# arduino_mega_2.net
KiCad netlist of a schematic drawn in EAGLE
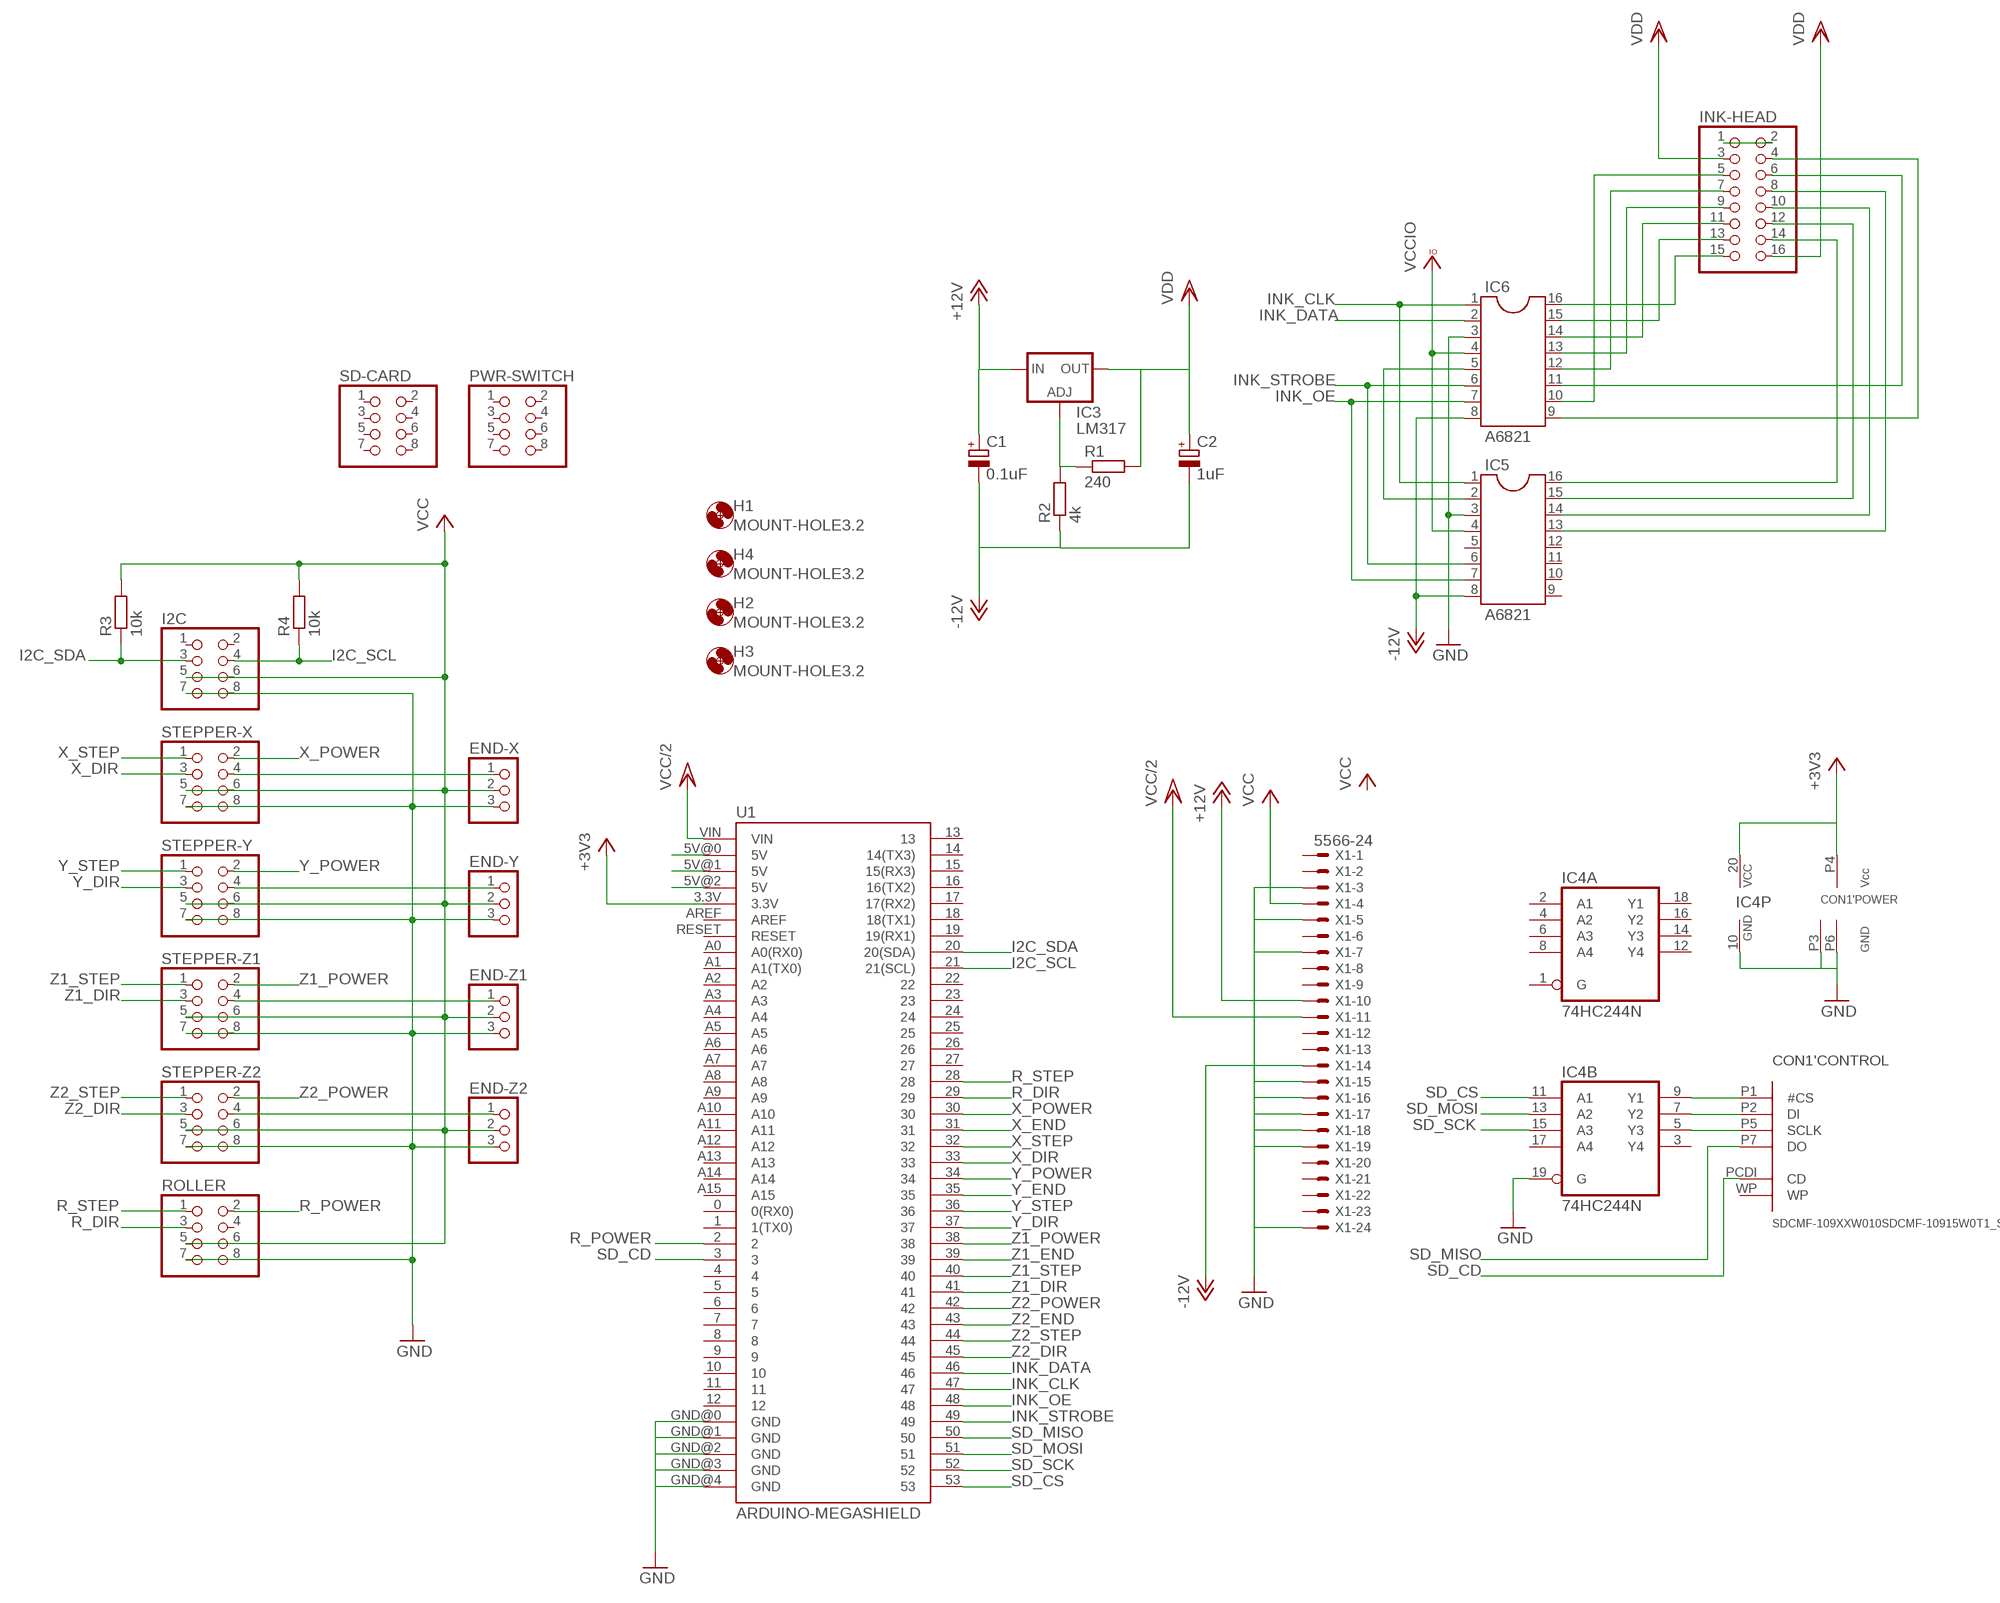
[diagram p0: schematic, sheet 1]

(export (version "E")
  (design (tool "Eeschema 10.0.6"))
  (components
    (comp (ref "C1")
      (value "0.1uF")
      (footprint "eagle-import:E2-5")
      (libsource (lib "eagle-import") (part "CPOL-EUE2-5"))
    )
    (comp (ref "C2")
      (value "1uF")
      (footprint "eagle-import:E2-5")
      (libsource (lib "eagle-import") (part "CPOL-EUE2-5"))
    )
    (comp (ref "CON1")
      (value "SDCMF-109XXW010SDCMF-10915W0T1_SO")
      (footprint "eagle-import:SDCMF-10915W0T1")
      (libsource (lib "eagle-import") (part "SDCMF-109XXW010SDCMF-10915W0T1_SO"))
    )
    (comp (ref "END-X")
      (value "PINHD-1X3")
      (footprint "eagle-import:1X03")
      (libsource (lib "eagle-import") (part "PINHD-1X3"))
    )
    (comp (ref "END-Y")
      (value "PINHD-1X3")
      (footprint "eagle-import:1X03")
      (libsource (lib "eagle-import") (part "PINHD-1X3"))
    )
    (comp (ref "END-Z1")
      (value "PINHD-1X3")
      (footprint "eagle-import:1X03")
      (libsource (lib "eagle-import") (part "PINHD-1X3"))
    )
    (comp (ref "END-Z2")
      (value "PINHD-1X3")
      (footprint "eagle-import:1X03")
      (libsource (lib "eagle-import") (part "PINHD-1X3"))
    )
    (comp (ref "H1")
      (value "MOUNT-HOLE3.2")
      (footprint "eagle-import:3,2")
      (libsource (lib "eagle-import") (part "MOUNT-HOLE3.2"))
    )
    (comp (ref "H2")
      (value "MOUNT-HOLE3.2")
      (footprint "eagle-import:3,2")
      (libsource (lib "eagle-import") (part "MOUNT-HOLE3.2"))
    )
    (comp (ref "H3")
      (value "MOUNT-HOLE3.2")
      (footprint "eagle-import:3,2")
      (libsource (lib "eagle-import") (part "MOUNT-HOLE3.2"))
    )
    (comp (ref "H4")
      (value "MOUNT-HOLE3.2")
      (footprint "eagle-import:3,2")
      (libsource (lib "eagle-import") (part "MOUNT-HOLE3.2"))
    )
    (comp (ref "I2C")
      (value "PINHD-2X4")
      (footprint "eagle-import:2X04")
      (libsource (lib "eagle-import") (part "PINHD-2X4"))
    )
    (comp (ref "IC3")
      (value "LM317")
      (footprint "eagle-import:317TL")
      (libsource (lib "eagle-import") (part "LM317TL"))
    )
    (comp (ref "IC4")
      (value "74HC244N")
      (footprint "eagle-import:DIL20")
      (libsource (lib "eagle-import") (part "74244NHC"))
    )
    (comp (ref "IC5")
      (value "A6821")
      (footprint "eagle-import:DIL16")
      (libsource (lib "eagle-import") (part "DIL16"))
    )
    (comp (ref "IC6")
      (value "A6821")
      (footprint "eagle-import:DIL16")
      (libsource (lib "eagle-import") (part "DIL16"))
    )
    (comp (ref "INK-HEAD")
      (value "PINHD-2X8")
      (footprint "eagle-import:2X08")
      (libsource (lib "eagle-import") (part "PINHD-2X8"))
    )
    (comp (ref "PWR-SWITCH")
      (value "PINHD-2X4")
      (footprint "eagle-import:2X04")
      (libsource (lib "eagle-import") (part "PINHD-2X4"))
    )
    (comp (ref "R1")
      (value "240")
      (footprint "eagle-import:0207_10")
      (libsource (lib "eagle-import") (part "R-EU_0207/10"))
    )
    (comp (ref "R2")
      (value "4k")
      (footprint "eagle-import:0207_10")
      (libsource (lib "eagle-import") (part "R-EU_0207/10"))
    )
    (comp (ref "R3")
      (value "10k")
      (footprint "eagle-import:0204_7")
      (libsource (lib "eagle-import") (part "R-EU_0204/7"))
    )
    (comp (ref "R4")
      (value "10k")
      (footprint "eagle-import:0204_7")
      (libsource (lib "eagle-import") (part "R-EU_0204/7"))
    )
    (comp (ref "ROLLER")
      (value "PINHD-2X4")
      (footprint "eagle-import:2X04")
      (libsource (lib "eagle-import") (part "PINHD-2X4"))
    )
    (comp (ref "SD-CARD")
      (value "PINHD-2X4")
      (footprint "eagle-import:2X04")
      (libsource (lib "eagle-import") (part "PINHD-2X4"))
    )
    (comp (ref "STEPPER-X")
      (value "PINHD-2X4")
      (footprint "eagle-import:2X04")
      (libsource (lib "eagle-import") (part "PINHD-2X4"))
    )
    (comp (ref "STEPPER-Y")
      (value "PINHD-2X4")
      (footprint "eagle-import:2X04")
      (libsource (lib "eagle-import") (part "PINHD-2X4"))
    )
    (comp (ref "STEPPER-Z1")
      (value "PINHD-2X4")
      (footprint "eagle-import:2X04")
      (libsource (lib "eagle-import") (part "PINHD-2X4"))
    )
    (comp (ref "STEPPER-Z2")
      (value "PINHD-2X4")
      (footprint "eagle-import:2X04")
      (libsource (lib "eagle-import") (part "PINHD-2X4"))
    )
    (comp (ref "U1")
      (value "ARDUINO-MEGASHIELD")
      (footprint "eagle-import:ARDUINO_MEGA_SHIELD")
      (libsource (lib "eagle-import") (part "ARDUINO-MEGASHIELD"))
    )
    (comp (ref "X1")
      (value "5566-24")
      (footprint "eagle-import:5566-24")
      (libsource (lib "eagle-import") (part "5566-24"))
    )
  )
  (nets
    (net (code "1") (name "+3V3") (class "Default")
      (node (ref "CON1") (pin "P4") (pinfunction "VCC_P4") (pintype "power_in"))
      (node (ref "IC4") (pin "20") (pinfunction "VCC_20") (pintype "power_in"))
      (node (ref "U1") (pin "3.3V") (pinfunction "3.3V_3.3V") (pintype "bidirectional"))
    )
    (net (code "2") (name "+12V") (class "Default")
      (node (ref "C1") (pin "+") (pinfunction "+_+") (pintype "passive"))
      (node (ref "IC3") (pin "3") (pinfunction "IN_3") (pintype "input"))
      (node (ref "X1") (pin "10") (pinfunction "S_10") (pintype "passive"))
    )
    (net (code "3") (name "-12V") (class "Default")
      (node (ref "C1") (pin "-") (pinfunction "-_-") (pintype "passive"))
      (node (ref "C2") (pin "-") (pinfunction "-_-") (pintype "passive"))
      (node (ref "IC5") (pin "8") (pinfunction "8_8") (pintype "passive"))
      (node (ref "IC6") (pin "8") (pinfunction "8_8") (pintype "passive"))
      (node (ref "R2") (pin "1") (pinfunction "1_1") (pintype "passive"))
      (node (ref "X1") (pin "14") (pinfunction "S_14") (pintype "passive"))
    )
    (net (code "4") (name "/I2C_SCL") (class "Default")
      (node (ref "I2C") (pin "4") (pinfunction "4_4") (pintype "passive"))
      (node (ref "R4") (pin "1") (pinfunction "1_1") (pintype "passive"))
      (node (ref "U1") (pin "21") (pinfunction "21(SCL)_21") (pintype "bidirectional"))
    )
    (net (code "5") (name "/I2C_SDA") (class "Default")
      (node (ref "I2C") (pin "3") (pinfunction "3_3") (pintype "passive"))
      (node (ref "R3") (pin "1") (pinfunction "1_1") (pintype "passive"))
      (node (ref "U1") (pin "20") (pinfunction "20(SDA)_20") (pintype "bidirectional"))
    )
    (net (code "6") (name "/INK_CLK") (class "Default")
      (node (ref "IC5") (pin "1") (pinfunction "1_1") (pintype "passive"))
      (node (ref "IC6") (pin "1") (pinfunction "1_1") (pintype "passive"))
      (node (ref "U1") (pin "47") (pinfunction "47_47") (pintype "bidirectional"))
    )
    (net (code "7") (name "/INK_DATA") (class "Default")
      (node (ref "IC6") (pin "2") (pinfunction "2_2") (pintype "passive"))
      (node (ref "U1") (pin "46") (pinfunction "46_46") (pintype "bidirectional"))
    )
    (net (code "8") (name "/INK_OE") (class "Default")
      (node (ref "IC5") (pin "7") (pinfunction "7_7") (pintype "passive"))
      (node (ref "IC6") (pin "7") (pinfunction "7_7") (pintype "passive"))
      (node (ref "U1") (pin "48") (pinfunction "48_48") (pintype "bidirectional"))
    )
    (net (code "9") (name "/INK_STROBE") (class "Default")
      (node (ref "IC5") (pin "6") (pinfunction "6_6") (pintype "passive"))
      (node (ref "IC6") (pin "6") (pinfunction "6_6") (pintype "passive"))
      (node (ref "U1") (pin "49") (pinfunction "49_49") (pintype "bidirectional"))
    )
    (net (code "10") (name "/R_DIR") (class "Default")
      (node (ref "ROLLER") (pin "3") (pinfunction "3_3") (pintype "passive"))
      (node (ref "U1") (pin "29") (pinfunction "29_29") (pintype "bidirectional"))
    )
    (net (code "11") (name "/R_POWER") (class "Default")
      (node (ref "ROLLER") (pin "2") (pinfunction "2_2") (pintype "passive"))
      (node (ref "U1") (pin "2") (pinfunction "2_2") (pintype "bidirectional"))
    )
    (net (code "12") (name "/R_STEP") (class "Default")
      (node (ref "ROLLER") (pin "1") (pinfunction "1_1") (pintype "passive"))
      (node (ref "U1") (pin "28") (pinfunction "28_28") (pintype "bidirectional"))
    )
    (net (code "13") (name "/SD_CD") (class "Default")
      (node (ref "CON1") (pin "PCDI") (pinfunction "CD_PCDI") (pintype "open_collector"))
      (node (ref "U1") (pin "3") (pinfunction "3_3") (pintype "bidirectional"))
    )
    (net (code "14") (name "/SD_CS") (class "Default")
      (node (ref "IC4") (pin "11") (pinfunction "A1_11") (pintype "input"))
      (node (ref "U1") (pin "53") (pinfunction "53_53") (pintype "bidirectional"))
    )
    (net (code "15") (name "/SD_MISO") (class "Default")
      (node (ref "CON1") (pin "P7") (pinfunction "DO_P7") (pintype "output"))
      (node (ref "U1") (pin "50") (pinfunction "50_50") (pintype "bidirectional"))
    )
    (net (code "16") (name "/SD_MOSI") (class "Default")
      (node (ref "IC4") (pin "13") (pinfunction "A2_13") (pintype "input"))
      (node (ref "U1") (pin "51") (pinfunction "51_51") (pintype "bidirectional"))
    )
    (net (code "17") (name "/SD_SCK") (class "Default")
      (node (ref "IC4") (pin "15") (pinfunction "A3_15") (pintype "input"))
      (node (ref "U1") (pin "52") (pinfunction "52_52") (pintype "bidirectional"))
    )
    (net (code "18") (name "/X_DIR") (class "Default")
      (node (ref "STEPPER-X") (pin "3") (pinfunction "3_3") (pintype "passive"))
      (node (ref "U1") (pin "33") (pinfunction "33_33") (pintype "bidirectional"))
    )
    (net (code "19") (name "/X_END") (class "Default")
      (node (ref "END-X") (pin "1") (pinfunction "1_1") (pintype "passive"))
      (node (ref "STEPPER-X") (pin "4") (pinfunction "4_4") (pintype "passive"))
      (node (ref "U1") (pin "31") (pinfunction "31_31") (pintype "bidirectional"))
    )
    (net (code "20") (name "/X_POWER") (class "Default")
      (node (ref "STEPPER-X") (pin "2") (pinfunction "2_2") (pintype "passive"))
      (node (ref "U1") (pin "30") (pinfunction "30_30") (pintype "bidirectional"))
    )
    (net (code "21") (name "/X_STEP") (class "Default")
      (node (ref "STEPPER-X") (pin "1") (pinfunction "1_1") (pintype "passive"))
      (node (ref "U1") (pin "32") (pinfunction "32_32") (pintype "bidirectional"))
    )
    (net (code "22") (name "/Y_DIR") (class "Default")
      (node (ref "STEPPER-Y") (pin "3") (pinfunction "3_3") (pintype "passive"))
      (node (ref "U1") (pin "37") (pinfunction "37_37") (pintype "bidirectional"))
    )
    (net (code "23") (name "/Y_END") (class "Default")
      (node (ref "END-Y") (pin "1") (pinfunction "1_1") (pintype "passive"))
      (node (ref "STEPPER-Y") (pin "4") (pinfunction "4_4") (pintype "passive"))
      (node (ref "U1") (pin "35") (pinfunction "35_35") (pintype "bidirectional"))
    )
    (net (code "24") (name "/Y_POWER") (class "Default")
      (node (ref "STEPPER-Y") (pin "2") (pinfunction "2_2") (pintype "passive"))
      (node (ref "U1") (pin "34") (pinfunction "34_34") (pintype "bidirectional"))
    )
    (net (code "25") (name "/Y_STEP") (class "Default")
      (node (ref "STEPPER-Y") (pin "1") (pinfunction "1_1") (pintype "passive"))
      (node (ref "U1") (pin "36") (pinfunction "36_36") (pintype "bidirectional"))
    )
    (net (code "26") (name "/Z1_DIR") (class "Default")
      (node (ref "STEPPER-Z1") (pin "3") (pinfunction "3_3") (pintype "passive"))
      (node (ref "U1") (pin "41") (pinfunction "41_41") (pintype "bidirectional"))
    )
    (net (code "27") (name "/Z1_END") (class "Default")
      (node (ref "END-Z1") (pin "1") (pinfunction "1_1") (pintype "passive"))
      (node (ref "STEPPER-Z1") (pin "4") (pinfunction "4_4") (pintype "passive"))
      (node (ref "U1") (pin "39") (pinfunction "39_39") (pintype "bidirectional"))
    )
    (net (code "28") (name "/Z1_POWER") (class "Default")
      (node (ref "STEPPER-Z1") (pin "2") (pinfunction "2_2") (pintype "passive"))
      (node (ref "U1") (pin "38") (pinfunction "38_38") (pintype "bidirectional"))
    )
    (net (code "29") (name "/Z1_STEP") (class "Default")
      (node (ref "STEPPER-Z1") (pin "1") (pinfunction "1_1") (pintype "passive"))
      (node (ref "U1") (pin "40") (pinfunction "40_40") (pintype "bidirectional"))
    )
    (net (code "30") (name "/Z2_DIR") (class "Default")
      (node (ref "STEPPER-Z2") (pin "3") (pinfunction "3_3") (pintype "passive"))
      (node (ref "U1") (pin "45") (pinfunction "45_45") (pintype "bidirectional"))
    )
    (net (code "31") (name "/Z2_END") (class "Default")
      (node (ref "END-Z2") (pin "1") (pinfunction "1_1") (pintype "passive"))
      (node (ref "STEPPER-Z2") (pin "4") (pinfunction "4_4") (pintype "passive"))
      (node (ref "U1") (pin "43") (pinfunction "43_43") (pintype "bidirectional"))
    )
    (net (code "32") (name "/Z2_POWER") (class "Default")
      (node (ref "STEPPER-Z2") (pin "2") (pinfunction "2_2") (pintype "passive"))
      (node (ref "U1") (pin "42") (pinfunction "42_42") (pintype "bidirectional"))
    )
    (net (code "33") (name "/Z2_STEP") (class "Default")
      (node (ref "STEPPER-Z2") (pin "1") (pinfunction "1_1") (pintype "passive"))
      (node (ref "U1") (pin "44") (pinfunction "44_44") (pintype "bidirectional"))
    )
    (net (code "34") (name "GND") (class "Default")
      (node (ref "CON1") (pin "P3") (pinfunction "GND_P3") (pintype "power_in"))
      (node (ref "CON1") (pin "P6") (pinfunction "GND_P6") (pintype "power_in"))
      (node (ref "END-X") (pin "3") (pinfunction "3_3") (pintype "passive"))
      (node (ref "END-Y") (pin "3") (pinfunction "3_3") (pintype "passive"))
      (node (ref "END-Z1") (pin "3") (pinfunction "3_3") (pintype "passive"))
      (node (ref "END-Z2") (pin "3") (pinfunction "3_3") (pintype "passive"))
      (node (ref "I2C") (pin "7") (pinfunction "7_7") (pintype "passive"))
      (node (ref "I2C") (pin "8") (pinfunction "8_8") (pintype "passive"))
      (node (ref "IC4") (pin "10") (pinfunction "GND_10") (pintype "power_in"))
      (node (ref "IC4") (pin "19") (pinfunction "G_19") (pintype "input"))
      (node (ref "IC5") (pin "3") (pinfunction "3_3") (pintype "passive"))
      (node (ref "IC6") (pin "3") (pinfunction "3_3") (pintype "passive"))
      (node (ref "ROLLER") (pin "7") (pinfunction "7_7") (pintype "passive"))
      (node (ref "ROLLER") (pin "8") (pinfunction "8_8") (pintype "passive"))
      (node (ref "STEPPER-X") (pin "7") (pinfunction "7_7") (pintype "passive"))
      (node (ref "STEPPER-X") (pin "8") (pinfunction "8_8") (pintype "passive"))
      (node (ref "STEPPER-Y") (pin "7") (pinfunction "7_7") (pintype "passive"))
      (node (ref "STEPPER-Y") (pin "8") (pinfunction "8_8") (pintype "passive"))
      (node (ref "STEPPER-Z1") (pin "7") (pinfunction "7_7") (pintype "passive"))
      (node (ref "STEPPER-Z1") (pin "8") (pinfunction "8_8") (pintype "passive"))
      (node (ref "STEPPER-Z2") (pin "7") (pinfunction "7_7") (pintype "passive"))
      (node (ref "STEPPER-Z2") (pin "8") (pinfunction "8_8") (pintype "passive"))
      (node (ref "U1") (pin "GND@0") (pinfunction "GND_GND@0") (pintype "bidirectional"))
      (node (ref "U1") (pin "GND@1") (pinfunction "GND_GND@1") (pintype "bidirectional"))
      (node (ref "U1") (pin "GND@2") (pinfunction "GND_GND@2") (pintype "bidirectional"))
      (node (ref "U1") (pin "GND@3") (pinfunction "GND_GND@3") (pintype "bidirectional"))
      (node (ref "U1") (pin "GND@4") (pinfunction "GND_GND@4") (pintype "bidirectional"))
      (node (ref "X1") (pin "15") (pinfunction "S_15") (pintype "passive"))
      (node (ref "X1") (pin "16") (pinfunction "S_16") (pintype "passive"))
      (node (ref "X1") (pin "17") (pinfunction "S_17") (pintype "passive"))
      (node (ref "X1") (pin "18") (pinfunction "S_18") (pintype "passive"))
      (node (ref "X1") (pin "19") (pinfunction "S_19") (pintype "passive"))
      (node (ref "X1") (pin "24") (pinfunction "S_24") (pintype "passive"))
      (node (ref "X1") (pin "3") (pinfunction "S_3") (pintype "passive"))
      (node (ref "X1") (pin "5") (pinfunction "S_5") (pintype "passive"))
      (node (ref "X1") (pin "7") (pinfunction "S_7") (pintype "passive"))
    )
    (net (code "35") (name "Net-(CON1A-#CS)") (class "Default")
      (node (ref "CON1") (pin "P1") (pinfunction "#CS_P1") (pintype "input"))
      (node (ref "IC4") (pin "9") (pinfunction "Y1_9") (pintype "tri_state"))
    )
    (net (code "36") (name "Net-(CON1A-DI)") (class "Default")
      (node (ref "CON1") (pin "P2") (pinfunction "DI_P2") (pintype "input"))
      (node (ref "IC4") (pin "7") (pinfunction "Y2_7") (pintype "tri_state"))
    )
    (net (code "37") (name "Net-(CON1A-SCLK)") (class "Default")
      (node (ref "CON1") (pin "P5") (pinfunction "SCLK_P5") (pintype "input"))
      (node (ref "IC4") (pin "5") (pinfunction "Y3_5") (pintype "tri_state"))
    )
    (net (code "38") (name "Net-(IC3-ADJ)") (class "Default")
      (node (ref "IC3") (pin "1") (pinfunction "ADJ_1") (pintype "input"))
      (node (ref "R1") (pin "1") (pinfunction "1_1") (pintype "passive"))
      (node (ref "R2") (pin "2") (pinfunction "2_2") (pintype "passive"))
    )
    (net (code "39") (name "Net-(IC5-Pad2)") (class "Default")
      (node (ref "IC5") (pin "2") (pinfunction "2_2") (pintype "passive"))
      (node (ref "IC6") (pin "5") (pinfunction "5_5") (pintype "passive"))
    )
    (net (code "40") (name "Net-(IC5-Pad13)") (class "Default")
      (node (ref "IC5") (pin "13") (pinfunction "13_13") (pintype "passive"))
      (node (ref "INK-HEAD") (pin "8") (pinfunction "8_8") (pintype "passive"))
    )
    (net (code "41") (name "Net-(IC5-Pad14)") (class "Default")
      (node (ref "IC5") (pin "14") (pinfunction "14_14") (pintype "passive"))
      (node (ref "INK-HEAD") (pin "10") (pinfunction "10_10") (pintype "passive"))
    )
    (net (code "42") (name "Net-(IC5-Pad15)") (class "Default")
      (node (ref "IC5") (pin "15") (pinfunction "15_15") (pintype "passive"))
      (node (ref "INK-HEAD") (pin "12") (pinfunction "12_12") (pintype "passive"))
    )
    (net (code "43") (name "Net-(IC5-Pad16)") (class "Default")
      (node (ref "IC5") (pin "16") (pinfunction "16_16") (pintype "passive"))
      (node (ref "INK-HEAD") (pin "14") (pinfunction "14_14") (pintype "passive"))
    )
    (net (code "44") (name "Net-(IC6-Pad9)") (class "Default")
      (node (ref "IC6") (pin "9") (pinfunction "9_9") (pintype "passive"))
      (node (ref "INK-HEAD") (pin "4") (pinfunction "4_4") (pintype "passive"))
    )
    (net (code "45") (name "Net-(IC6-Pad10)") (class "Default")
      (node (ref "IC6") (pin "10") (pinfunction "10_10") (pintype "passive"))
      (node (ref "INK-HEAD") (pin "5") (pinfunction "5_5") (pintype "passive"))
    )
    (net (code "46") (name "Net-(IC6-Pad11)") (class "Default")
      (node (ref "IC6") (pin "11") (pinfunction "11_11") (pintype "passive"))
      (node (ref "INK-HEAD") (pin "6") (pinfunction "6_6") (pintype "passive"))
    )
    (net (code "47") (name "Net-(IC6-Pad12)") (class "Default")
      (node (ref "IC6") (pin "12") (pinfunction "12_12") (pintype "passive"))
      (node (ref "INK-HEAD") (pin "7") (pinfunction "7_7") (pintype "passive"))
    )
    (net (code "48") (name "Net-(IC6-Pad13)") (class "Default")
      (node (ref "IC6") (pin "13") (pinfunction "13_13") (pintype "passive"))
      (node (ref "INK-HEAD") (pin "9") (pinfunction "9_9") (pintype "passive"))
    )
    (net (code "49") (name "Net-(IC6-Pad14)") (class "Default")
      (node (ref "IC6") (pin "14") (pinfunction "14_14") (pintype "passive"))
      (node (ref "INK-HEAD") (pin "11") (pinfunction "11_11") (pintype "passive"))
    )
    (net (code "50") (name "Net-(IC6-Pad15)") (class "Default")
      (node (ref "IC6") (pin "15") (pinfunction "15_15") (pintype "passive"))
      (node (ref "INK-HEAD") (pin "13") (pinfunction "13_13") (pintype "passive"))
    )
    (net (code "51") (name "Net-(IC6-Pad16)") (class "Default")
      (node (ref "IC6") (pin "16") (pinfunction "16_16") (pintype "passive"))
      (node (ref "INK-HEAD") (pin "15") (pinfunction "15_15") (pintype "passive"))
    )
    (net (code "52") (name "Net-(INK-HEAD-Pad1)") (class "Default")
      (node (ref "INK-HEAD") (pin "1") (pinfunction "1_1") (pintype "passive"))
      (node (ref "INK-HEAD") (pin "2") (pinfunction "2_2") (pintype "passive"))
    )
    (net (code "53") (name "VCC") (class "Default")
      (node (ref "END-X") (pin "2") (pinfunction "2_2") (pintype "passive"))
      (node (ref "END-Y") (pin "2") (pinfunction "2_2") (pintype "passive"))
      (node (ref "END-Z1") (pin "2") (pinfunction "2_2") (pintype "passive"))
      (node (ref "END-Z2") (pin "2") (pinfunction "2_2") (pintype "passive"))
      (node (ref "I2C") (pin "5") (pinfunction "5_5") (pintype "passive"))
      (node (ref "I2C") (pin "6") (pinfunction "6_6") (pintype "passive"))
      (node (ref "R3") (pin "2") (pinfunction "2_2") (pintype "passive"))
      (node (ref "R4") (pin "2") (pinfunction "2_2") (pintype "passive"))
      (node (ref "ROLLER") (pin "5") (pinfunction "5_5") (pintype "passive"))
      (node (ref "ROLLER") (pin "6") (pinfunction "6_6") (pintype "passive"))
      (node (ref "STEPPER-X") (pin "5") (pinfunction "5_5") (pintype "passive"))
      (node (ref "STEPPER-X") (pin "6") (pinfunction "6_6") (pintype "passive"))
      (node (ref "STEPPER-Y") (pin "5") (pinfunction "5_5") (pintype "passive"))
      (node (ref "STEPPER-Y") (pin "6") (pinfunction "6_6") (pintype "passive"))
      (node (ref "STEPPER-Z1") (pin "5") (pinfunction "5_5") (pintype "passive"))
      (node (ref "STEPPER-Z1") (pin "6") (pinfunction "6_6") (pintype "passive"))
      (node (ref "STEPPER-Z2") (pin "5") (pinfunction "5_5") (pintype "passive"))
      (node (ref "STEPPER-Z2") (pin "6") (pinfunction "6_6") (pintype "passive"))
      (node (ref "X1") (pin "4") (pinfunction "S_4") (pintype "passive"))
    )
    (net (code "54") (name "VCCIO") (class "Default")
      (node (ref "IC5") (pin "4") (pinfunction "4_4") (pintype "passive"))
      (node (ref "IC6") (pin "4") (pinfunction "4_4") (pintype "passive"))
      (node (ref "U1") (pin "5V@0") (pinfunction "5V_5V@0") (pintype "bidirectional"))
      (node (ref "U1") (pin "5V@1") (pinfunction "5V_5V@1") (pintype "bidirectional"))
      (node (ref "U1") (pin "5V@2") (pinfunction "5V_5V@2") (pintype "bidirectional"))
    )
    (net (code "55") (name "VCC{slash}2") (class "Default")
      (node (ref "U1") (pin "VIN") (pinfunction "VIN_VIN") (pintype "bidirectional"))
      (node (ref "X1") (pin "11") (pinfunction "S_11") (pintype "passive"))
    )
    (net (code "56") (name "VDD") (class "Default")
      (node (ref "C2") (pin "+") (pinfunction "+_+") (pintype "passive"))
      (node (ref "IC3") (pin "2") (pinfunction "OUT_2") (pintype "passive"))
      (node (ref "INK-HEAD") (pin "16") (pinfunction "16_16") (pintype "passive"))
      (node (ref "INK-HEAD") (pin "3") (pinfunction "3_3") (pintype "passive"))
      (node (ref "R1") (pin "2") (pinfunction "2_2") (pintype "passive"))
    )
    (net (code "57") (name "unconnected-(CON1-PadWP)") (class "Default")
      (node (ref "CON1") (pin "WP") (pinfunction "WP_WP") (pintype "open_collector"))
    )
    (net (code "58") (name "unconnected-(I2C-Pad1)") (class "Default")
      (node (ref "I2C") (pin "1") (pinfunction "1_1") (pintype "passive"))
    )
    (net (code "59") (name "unconnected-(I2C-Pad2)") (class "Default")
      (node (ref "I2C") (pin "2") (pinfunction "2_2") (pintype "passive"))
    )
    (net (code "60") (name "unconnected-(IC4A-A1-Pad2)") (class "Default")
      (node (ref "IC4") (pin "2") (pinfunction "A1_2") (pintype "input"))
    )
    (net (code "61") (name "unconnected-(IC4A-A2-Pad4)") (class "Default")
      (node (ref "IC4") (pin "4") (pinfunction "A2_4") (pintype "input"))
    )
    (net (code "62") (name "unconnected-(IC4A-A3-Pad6)") (class "Default")
      (node (ref "IC4") (pin "6") (pinfunction "A3_6") (pintype "input"))
    )
    (net (code "63") (name "unconnected-(IC4A-A4-Pad8)") (class "Default")
      (node (ref "IC4") (pin "8") (pinfunction "A4_8") (pintype "input"))
    )
    (net (code "64") (name "unconnected-(IC4A-G-Pad1)") (class "Default")
      (node (ref "IC4") (pin "1") (pinfunction "G_1") (pintype "input"))
    )
    (net (code "65") (name "unconnected-(IC4A-Y1-Pad18)") (class "Default")
      (node (ref "IC4") (pin "18") (pinfunction "Y1_18") (pintype "tri_state"))
    )
    (net (code "66") (name "unconnected-(IC4A-Y2-Pad16)") (class "Default")
      (node (ref "IC4") (pin "16") (pinfunction "Y2_16") (pintype "tri_state"))
    )
    (net (code "67") (name "unconnected-(IC4A-Y3-Pad14)") (class "Default")
      (node (ref "IC4") (pin "14") (pinfunction "Y3_14") (pintype "tri_state"))
    )
    (net (code "68") (name "unconnected-(IC4A-Y4-Pad12)") (class "Default")
      (node (ref "IC4") (pin "12") (pinfunction "Y4_12") (pintype "tri_state"))
    )
    (net (code "69") (name "unconnected-(IC4B-A4-Pad17)") (class "Default")
      (node (ref "IC4") (pin "17") (pinfunction "A4_17") (pintype "input"))
    )
    (net (code "70") (name "unconnected-(IC4B-Y4-Pad3)") (class "Default")
      (node (ref "IC4") (pin "3") (pinfunction "Y4_3") (pintype "tri_state"))
    )
    (net (code "71") (name "unconnected-(IC5-Pad5)") (class "Default")
      (node (ref "IC5") (pin "5") (pinfunction "5_5") (pintype "passive"))
    )
    (net (code "72") (name "unconnected-(IC5-Pad9)") (class "Default")
      (node (ref "IC5") (pin "9") (pinfunction "9_9") (pintype "passive"))
    )
    (net (code "73") (name "unconnected-(IC5-Pad10)") (class "Default")
      (node (ref "IC5") (pin "10") (pinfunction "10_10") (pintype "passive"))
    )
    (net (code "74") (name "unconnected-(IC5-Pad11)") (class "Default")
      (node (ref "IC5") (pin "11") (pinfunction "11_11") (pintype "passive"))
    )
    (net (code "75") (name "unconnected-(IC5-Pad12)") (class "Default")
      (node (ref "IC5") (pin "12") (pinfunction "12_12") (pintype "passive"))
    )
    (net (code "76") (name "unconnected-(PWR-SWITCH-Pad1)") (class "Default")
      (node (ref "PWR-SWITCH") (pin "1") (pinfunction "1_1") (pintype "passive"))
    )
    (net (code "77") (name "unconnected-(PWR-SWITCH-Pad2)") (class "Default")
      (node (ref "PWR-SWITCH") (pin "2") (pinfunction "2_2") (pintype "passive"))
    )
    (net (code "78") (name "unconnected-(PWR-SWITCH-Pad3)") (class "Default")
      (node (ref "PWR-SWITCH") (pin "3") (pinfunction "3_3") (pintype "passive"))
    )
    (net (code "79") (name "unconnected-(PWR-SWITCH-Pad4)") (class "Default")
      (node (ref "PWR-SWITCH") (pin "4") (pinfunction "4_4") (pintype "passive"))
    )
    (net (code "80") (name "unconnected-(PWR-SWITCH-Pad5)") (class "Default")
      (node (ref "PWR-SWITCH") (pin "5") (pinfunction "5_5") (pintype "passive"))
    )
    (net (code "81") (name "unconnected-(PWR-SWITCH-Pad6)") (class "Default")
      (node (ref "PWR-SWITCH") (pin "6") (pinfunction "6_6") (pintype "passive"))
    )
    (net (code "82") (name "unconnected-(PWR-SWITCH-Pad7)") (class "Default")
      (node (ref "PWR-SWITCH") (pin "7") (pinfunction "7_7") (pintype "passive"))
    )
    (net (code "83") (name "unconnected-(PWR-SWITCH-Pad8)") (class "Default")
      (node (ref "PWR-SWITCH") (pin "8") (pinfunction "8_8") (pintype "passive"))
    )
    (net (code "84") (name "unconnected-(ROLLER-Pad4)") (class "Default")
      (node (ref "ROLLER") (pin "4") (pinfunction "4_4") (pintype "passive"))
    )
    (net (code "85") (name "unconnected-(SD-CARD-Pad1)") (class "Default")
      (node (ref "SD-CARD") (pin "1") (pinfunction "1_1") (pintype "passive"))
    )
    (net (code "86") (name "unconnected-(SD-CARD-Pad2)") (class "Default")
      (node (ref "SD-CARD") (pin "2") (pinfunction "2_2") (pintype "passive"))
    )
    (net (code "87") (name "unconnected-(SD-CARD-Pad3)") (class "Default")
      (node (ref "SD-CARD") (pin "3") (pinfunction "3_3") (pintype "passive"))
    )
    (net (code "88") (name "unconnected-(SD-CARD-Pad4)") (class "Default")
      (node (ref "SD-CARD") (pin "4") (pinfunction "4_4") (pintype "passive"))
    )
    (net (code "89") (name "unconnected-(SD-CARD-Pad5)") (class "Default")
      (node (ref "SD-CARD") (pin "5") (pinfunction "5_5") (pintype "passive"))
    )
    (net (code "90") (name "unconnected-(SD-CARD-Pad6)") (class "Default")
      (node (ref "SD-CARD") (pin "6") (pinfunction "6_6") (pintype "passive"))
    )
    (net (code "91") (name "unconnected-(SD-CARD-Pad7)") (class "Default")
      (node (ref "SD-CARD") (pin "7") (pinfunction "7_7") (pintype "passive"))
    )
    (net (code "92") (name "unconnected-(SD-CARD-Pad8)") (class "Default")
      (node (ref "SD-CARD") (pin "8") (pinfunction "8_8") (pintype "passive"))
    )
    (net (code "93") (name "unconnected-(U1-0(RX0)-Pad0)") (class "Default")
      (node (ref "U1") (pin "0") (pinfunction "0(RX0)_0") (pintype "bidirectional"))
    )
    (net (code "94") (name "unconnected-(U1-1(TX0)-Pad1)") (class "Default")
      (node (ref "U1") (pin "1") (pinfunction "1(TX0)_1") (pintype "bidirectional"))
    )
    (net (code "95") (name "unconnected-(U1-14(TX3)-Pad14)") (class "Default")
      (node (ref "U1") (pin "14") (pinfunction "14(TX3)_14") (pintype "bidirectional"))
    )
    (net (code "96") (name "unconnected-(U1-15(RX3)-Pad15)") (class "Default")
      (node (ref "U1") (pin "15") (pinfunction "15(RX3)_15") (pintype "bidirectional"))
    )
    (net (code "97") (name "unconnected-(U1-16(TX2)-Pad16)") (class "Default")
      (node (ref "U1") (pin "16") (pinfunction "16(TX2)_16") (pintype "bidirectional"))
    )
    (net (code "98") (name "unconnected-(U1-17(RX2)-Pad17)") (class "Default")
      (node (ref "U1") (pin "17") (pinfunction "17(RX2)_17") (pintype "bidirectional"))
    )
    (net (code "99") (name "unconnected-(U1-18(TX1)-Pad18)") (class "Default")
      (node (ref "U1") (pin "18") (pinfunction "18(TX1)_18") (pintype "bidirectional"))
    )
    (net (code "100") (name "unconnected-(U1-19(RX1)-Pad19)") (class "Default")
      (node (ref "U1") (pin "19") (pinfunction "19(RX1)_19") (pintype "bidirectional"))
    )
    (net (code "101") (name "unconnected-(U1-A0(RX0)-PadA0)") (class "Default")
      (node (ref "U1") (pin "A0") (pinfunction "A0(RX0)_A0") (pintype "bidirectional"))
    )
    (net (code "102") (name "unconnected-(U1-A1(TX0)-PadA1)") (class "Default")
      (node (ref "U1") (pin "A1") (pinfunction "A1(TX0)_A1") (pintype "bidirectional"))
    )
    (net (code "103") (name "unconnected-(U1-Pad4)") (class "Default")
      (node (ref "U1") (pin "4") (pinfunction "4_4") (pintype "bidirectional"))
    )
    (net (code "104") (name "unconnected-(U1-Pad5)") (class "Default")
      (node (ref "U1") (pin "5") (pinfunction "5_5") (pintype "bidirectional"))
    )
    (net (code "105") (name "unconnected-(U1-Pad6)") (class "Default")
      (node (ref "U1") (pin "6") (pinfunction "6_6") (pintype "bidirectional"))
    )
    (net (code "106") (name "unconnected-(U1-Pad7)") (class "Default")
      (node (ref "U1") (pin "7") (pinfunction "7_7") (pintype "bidirectional"))
    )
    (net (code "107") (name "unconnected-(U1-Pad8)") (class "Default")
      (node (ref "U1") (pin "8") (pinfunction "8_8") (pintype "bidirectional"))
    )
    (net (code "108") (name "unconnected-(U1-Pad9)") (class "Default")
      (node (ref "U1") (pin "9") (pinfunction "9_9") (pintype "bidirectional"))
    )
    (net (code "109") (name "unconnected-(U1-Pad10)") (class "Default")
      (node (ref "U1") (pin "10") (pinfunction "10_10") (pintype "bidirectional"))
    )
    (net (code "110") (name "unconnected-(U1-Pad11)") (class "Default")
      (node (ref "U1") (pin "11") (pinfunction "11_11") (pintype "bidirectional"))
    )
    (net (code "111") (name "unconnected-(U1-Pad12)") (class "Default")
      (node (ref "U1") (pin "12") (pinfunction "12_12") (pintype "bidirectional"))
    )
    (net (code "112") (name "unconnected-(U1-Pad13)") (class "Default")
      (node (ref "U1") (pin "13") (pinfunction "13_13") (pintype "bidirectional"))
    )
    (net (code "113") (name "unconnected-(U1-Pad22)") (class "Default")
      (node (ref "U1") (pin "22") (pinfunction "22_22") (pintype "bidirectional"))
    )
    (net (code "114") (name "unconnected-(U1-Pad23)") (class "Default")
      (node (ref "U1") (pin "23") (pinfunction "23_23") (pintype "bidirectional"))
    )
    (net (code "115") (name "unconnected-(U1-Pad24)") (class "Default")
      (node (ref "U1") (pin "24") (pinfunction "24_24") (pintype "bidirectional"))
    )
    (net (code "116") (name "unconnected-(U1-Pad25)") (class "Default")
      (node (ref "U1") (pin "25") (pinfunction "25_25") (pintype "bidirectional"))
    )
    (net (code "117") (name "unconnected-(U1-Pad26)") (class "Default")
      (node (ref "U1") (pin "26") (pinfunction "26_26") (pintype "bidirectional"))
    )
    (net (code "118") (name "unconnected-(U1-Pad27)") (class "Default")
      (node (ref "U1") (pin "27") (pinfunction "27_27") (pintype "bidirectional"))
    )
    (net (code "119") (name "unconnected-(U1-PadA2)") (class "Default")
      (node (ref "U1") (pin "A2") (pinfunction "A2_A2") (pintype "bidirectional"))
    )
    (net (code "120") (name "unconnected-(U1-PadA3)") (class "Default")
      (node (ref "U1") (pin "A3") (pinfunction "A3_A3") (pintype "bidirectional"))
    )
    (net (code "121") (name "unconnected-(U1-PadA4)") (class "Default")
      (node (ref "U1") (pin "A4") (pinfunction "A4_A4") (pintype "bidirectional"))
    )
    (net (code "122") (name "unconnected-(U1-PadA5)") (class "Default")
      (node (ref "U1") (pin "A5") (pinfunction "A5_A5") (pintype "bidirectional"))
    )
    (net (code "123") (name "unconnected-(U1-PadA6)") (class "Default")
      (node (ref "U1") (pin "A6") (pinfunction "A6_A6") (pintype "bidirectional"))
    )
    (net (code "124") (name "unconnected-(U1-PadA7)") (class "Default")
      (node (ref "U1") (pin "A7") (pinfunction "A7_A7") (pintype "bidirectional"))
    )
    (net (code "125") (name "unconnected-(U1-PadA8)") (class "Default")
      (node (ref "U1") (pin "A8") (pinfunction "A8_A8") (pintype "bidirectional"))
    )
    (net (code "126") (name "unconnected-(U1-PadA9)") (class "Default")
      (node (ref "U1") (pin "A9") (pinfunction "A9_A9") (pintype "bidirectional"))
    )
    (net (code "127") (name "unconnected-(U1-PadA10)") (class "Default")
      (node (ref "U1") (pin "A10") (pinfunction "A10_A10") (pintype "bidirectional"))
    )
    (net (code "128") (name "unconnected-(U1-PadA11)") (class "Default")
      (node (ref "U1") (pin "A11") (pinfunction "A11_A11") (pintype "bidirectional"))
    )
    (net (code "129") (name "unconnected-(U1-PadA12)") (class "Default")
      (node (ref "U1") (pin "A12") (pinfunction "A12_A12") (pintype "bidirectional"))
    )
    (net (code "130") (name "unconnected-(U1-PadA13)") (class "Default")
      (node (ref "U1") (pin "A13") (pinfunction "A13_A13") (pintype "bidirectional"))
    )
    (net (code "131") (name "unconnected-(U1-PadA14)") (class "Default")
      (node (ref "U1") (pin "A14") (pinfunction "A14_A14") (pintype "bidirectional"))
    )
    (net (code "132") (name "unconnected-(U1-PadA15)") (class "Default")
      (node (ref "U1") (pin "A15") (pinfunction "A15_A15") (pintype "bidirectional"))
    )
    (net (code "133") (name "unconnected-(U1-PadAREF)") (class "Default")
      (node (ref "U1") (pin "AREF") (pinfunction "AREF_AREF") (pintype "bidirectional"))
    )
    (net (code "134") (name "unconnected-(U1-PadRESET)") (class "Default")
      (node (ref "U1") (pin "RESET") (pinfunction "RESET_RESET") (pintype "bidirectional"))
    )
    (net (code "135") (name "unconnected-(X1A-S-Pad1)") (class "Default")
      (node (ref "X1") (pin "1") (pinfunction "S_1") (pintype "passive"))
    )
    (net (code "136") (name "unconnected-(X1D-S-Pad12)") (class "Default")
      (node (ref "X1") (pin "12") (pinfunction "S_12") (pintype "passive"))
    )
    (net (code "137") (name "unconnected-(X1E-S-Pad13)") (class "Default")
      (node (ref "X1") (pin "13") (pinfunction "S_13") (pintype "passive"))
    )
    (net (code "138") (name "unconnected-(X1L-S-Pad2)") (class "Default")
      (node (ref "X1") (pin "2") (pinfunction "S_2") (pintype "passive"))
    )
    (net (code "139") (name "unconnected-(X1M-S-Pad20)") (class "Default")
      (node (ref "X1") (pin "20") (pinfunction "S_20") (pintype "passive"))
    )
    (net (code "140") (name "unconnected-(X1N-S-Pad21)") (class "Default")
      (node (ref "X1") (pin "21") (pinfunction "S_21") (pintype "passive"))
    )
    (net (code "141") (name "unconnected-(X1O-S-Pad22)") (class "Default")
      (node (ref "X1") (pin "22") (pinfunction "S_22") (pintype "passive"))
    )
    (net (code "142") (name "unconnected-(X1P-S-Pad23)") (class "Default")
      (node (ref "X1") (pin "23") (pinfunction "S_23") (pintype "passive"))
    )
    (net (code "143") (name "unconnected-(X1U-S-Pad6)") (class "Default")
      (node (ref "X1") (pin "6") (pinfunction "S_6") (pintype "passive"))
    )
    (net (code "144") (name "unconnected-(X1W-S-Pad8)") (class "Default")
      (node (ref "X1") (pin "8") (pinfunction "S_8") (pintype "passive"))
    )
    (net (code "145") (name "unconnected-(X1X-S-Pad9)") (class "Default")
      (node (ref "X1") (pin "9") (pinfunction "S_9") (pintype "passive"))
    )
  )
)
